# NextTouch.net
KiCad netlist of a schematic drawn in EAGLE
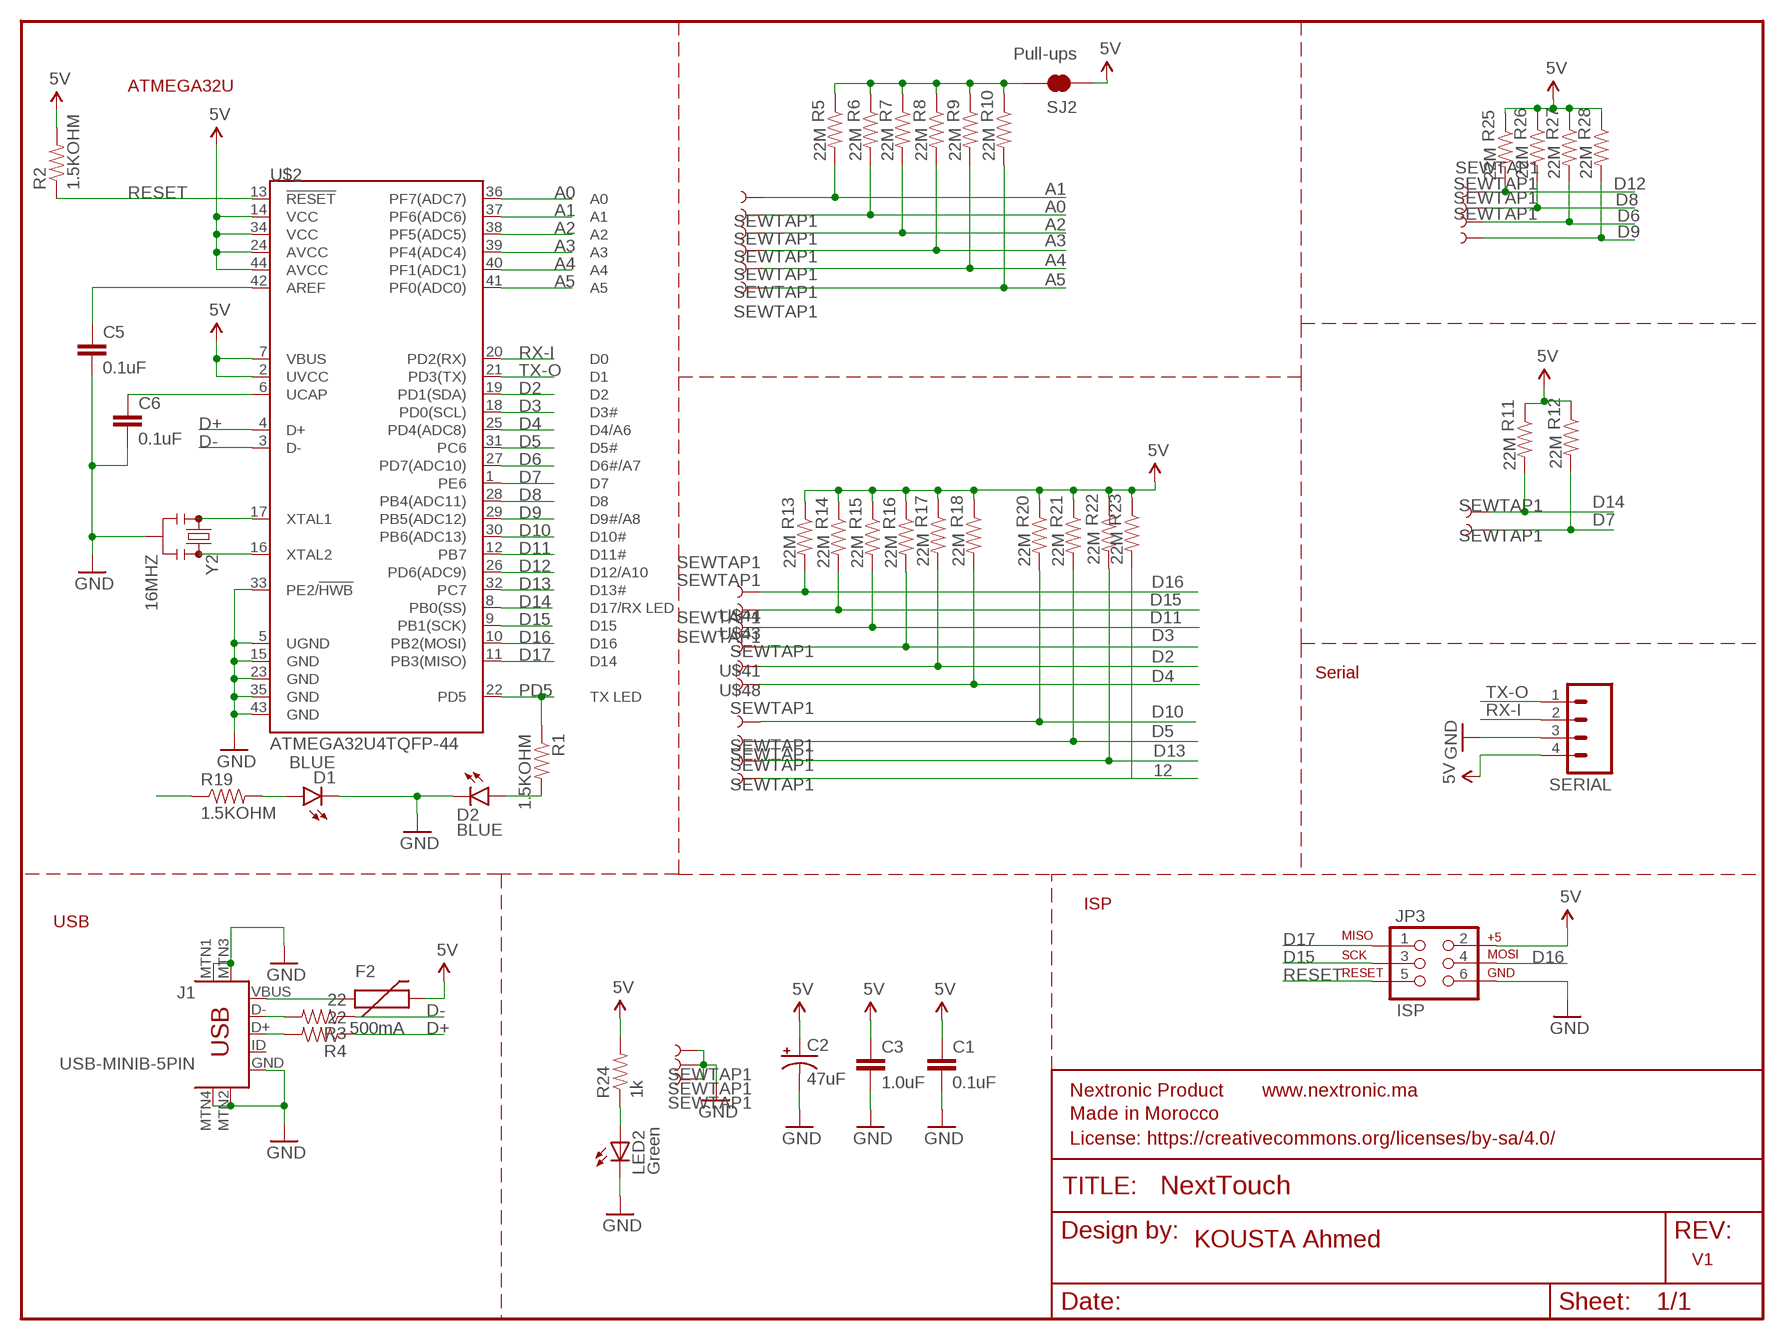
[diagram p0: schematic, sheet 1]

(export (version "E")
  (design (tool "Eeschema 10.0.6"))
  (components
    (comp (ref "C1")
      (value "0.1uF")
      (footprint "eagle-import:0603")
      (libsource (lib "eagle-import") (part "CAP0603"))
    )
    (comp (ref "C2")
      (value "47uF")
      (footprint "eagle-import:EIA3528")
      (libsource (lib "eagle-import") (part "CAP_POL3528"))
    )
    (comp (ref "C3")
      (value "1.0uF")
      (footprint "eagle-import:0603")
      (libsource (lib "eagle-import") (part "CAP0603"))
    )
    (comp (ref "C5")
      (value "0.1uF")
      (footprint "eagle-import:0603")
      (libsource (lib "eagle-import") (part "0.18UF-10V(+-10%)(0603)"))
    )
    (comp (ref "C6")
      (value "0.1uF")
      (footprint "eagle-import:0603")
      (libsource (lib "eagle-import") (part "0.18UF-10V(+-10%)(0603)"))
    )
    (comp (ref "D1")
      (value "BLUE")
      (footprint "eagle-import:LED-1206")
      (libsource (lib "eagle-import") (part "LED-BLUE1206"))
    )
    (comp (ref "D2")
      (value "BLUE")
      (footprint "eagle-import:LED-1206")
      (libsource (lib "eagle-import") (part "LED-BLUE1206"))
    )
    (comp (ref "F2")
      (value "500mA")
      (footprint "eagle-import:PTC-1206")
      (libsource (lib "eagle-import") (part "PTCSMD"))
    )
    (comp (ref "FRAME1")
      (value "FRAME-LETTER")
      (footprint "eagle-import:CREATIVE_COMMONS")
      (libsource (lib "eagle-import") (part "FRAME-LETTER"))
    )
    (comp (ref "GND")
      (value "SEWTAP1")
      (footprint "eagle-import:PETAL-LONG-1")
      (libsource (lib "eagle-import") (part "SEWTAP1"))
    )
    (comp (ref "J1")
      (value "USB-MINIB-5PIN")
      (footprint "eagle-import:USB-MINIB")
      (libsource (lib "eagle-import") (part "USB-MINIB-5PIN"))
    )
    (comp (ref "JP3")
      (value "ISP")
      (footprint "eagle-import:2X3-NS")
      (libsource (lib "eagle-import") (part "AVR_SPI_PRG_6NS"))
    )
    (comp (ref "LED2")
      (value "Green")
      (footprint "eagle-import:LED-1206-NO_SILK")
      (libsource (lib "eagle-import") (part "LED1206-NS"))
    )
    (comp (ref "R1")
      (value "1.5KOHM")
      (footprint "eagle-import:0603")
      (libsource (lib "eagle-import") (part "1.5KOHM-1/10W-1%(0603)"))
    )
    (comp (ref "R2")
      (value "1.5KOHM")
      (footprint "eagle-import:0603")
      (libsource (lib "eagle-import") (part "1.5KOHM-1/10W-1%(0603)"))
    )
    (comp (ref "R3")
      (value "22")
      (footprint "eagle-import:0603")
      (libsource (lib "eagle-import") (part "1.5KOHM-1/10W-1%(0603)"))
    )
    (comp (ref "R4")
      (value "22")
      (footprint "eagle-import:0603")
      (libsource (lib "eagle-import") (part "1.5KOHM-1/10W-1%(0603)"))
    )
    (comp (ref "R5")
      (value "22M")
      (footprint "eagle-import:0603")
      (libsource (lib "eagle-import") (part "1.5KOHM-1/10W-1%(0603)"))
    )
    (comp (ref "R6")
      (value "22M")
      (footprint "eagle-import:0603")
      (libsource (lib "eagle-import") (part "1.5KOHM-1/10W-1%(0603)"))
    )
    (comp (ref "R7")
      (value "22M")
      (footprint "eagle-import:0603")
      (libsource (lib "eagle-import") (part "1.5KOHM-1/10W-1%(0603)"))
    )
    (comp (ref "R8")
      (value "22M")
      (footprint "eagle-import:0603")
      (libsource (lib "eagle-import") (part "1.5KOHM-1/10W-1%(0603)"))
    )
    (comp (ref "R9")
      (value "22M")
      (footprint "eagle-import:0603")
      (libsource (lib "eagle-import") (part "1.5KOHM-1/10W-1%(0603)"))
    )
    (comp (ref "R10")
      (value "22M")
      (footprint "eagle-import:0603")
      (libsource (lib "eagle-import") (part "1.5KOHM-1/10W-1%(0603)"))
    )
    (comp (ref "R11")
      (value "22M")
      (footprint "eagle-import:0603")
      (libsource (lib "eagle-import") (part "1.5KOHM-1/10W-1%(0603)"))
    )
    (comp (ref "R12")
      (value "22M")
      (footprint "eagle-import:0603")
      (libsource (lib "eagle-import") (part "1.5KOHM-1/10W-1%(0603)"))
    )
    (comp (ref "R13")
      (value "22M")
      (footprint "eagle-import:0603")
      (libsource (lib "eagle-import") (part "1.5KOHM-1/10W-1%(0603)"))
    )
    (comp (ref "R14")
      (value "22M")
      (footprint "eagle-import:0603")
      (libsource (lib "eagle-import") (part "1.5KOHM-1/10W-1%(0603)"))
    )
    (comp (ref "R15")
      (value "22M")
      (footprint "eagle-import:0603")
      (libsource (lib "eagle-import") (part "1.5KOHM-1/10W-1%(0603)"))
    )
    (comp (ref "R16")
      (value "22M")
      (footprint "eagle-import:0603")
      (libsource (lib "eagle-import") (part "1.5KOHM-1/10W-1%(0603)"))
    )
    (comp (ref "R17")
      (value "22M")
      (footprint "eagle-import:0603")
      (libsource (lib "eagle-import") (part "1.5KOHM-1/10W-1%(0603)"))
    )
    (comp (ref "R18")
      (value "22M")
      (footprint "eagle-import:0603")
      (libsource (lib "eagle-import") (part "1.5KOHM-1/10W-1%(0603)"))
    )
    (comp (ref "R19")
      (value "1.5KOHM")
      (footprint "eagle-import:0603")
      (libsource (lib "eagle-import") (part "1.5KOHM-1/10W-1%(0603)"))
    )
    (comp (ref "R20")
      (value "22M")
      (footprint "eagle-import:0603")
      (libsource (lib "eagle-import") (part "1.5KOHM-1/10W-1%(0603)"))
    )
    (comp (ref "R21")
      (value "22M")
      (footprint "eagle-import:0603")
      (libsource (lib "eagle-import") (part "1.5KOHM-1/10W-1%(0603)"))
    )
    (comp (ref "R22")
      (value "22M")
      (footprint "eagle-import:0603")
      (libsource (lib "eagle-import") (part "1.5KOHM-1/10W-1%(0603)"))
    )
    (comp (ref "R23")
      (value "22M")
      (footprint "eagle-import:0603")
      (libsource (lib "eagle-import") (part "1.5KOHM-1/10W-1%(0603)"))
    )
    (comp (ref "R24")
      (value "1k")
      (footprint "eagle-import:0603-RES")
      (libsource (lib "eagle-import") (part "RESISTOR0603-RES"))
    )
    (comp (ref "R25")
      (value "22M")
      (footprint "eagle-import:0603")
      (libsource (lib "eagle-import") (part "1.5KOHM-1/10W-1%(0603)"))
    )
    (comp (ref "R26")
      (value "22M")
      (footprint "eagle-import:0603")
      (libsource (lib "eagle-import") (part "1.5KOHM-1/10W-1%(0603)"))
    )
    (comp (ref "R27")
      (value "22M")
      (footprint "eagle-import:0603")
      (libsource (lib "eagle-import") (part "1.5KOHM-1/10W-1%(0603)"))
    )
    (comp (ref "R28")
      (value "22M")
      (footprint "eagle-import:0603")
      (libsource (lib "eagle-import") (part "1.5KOHM-1/10W-1%(0603)"))
    )
    (comp (ref "SERIAL")
      (value "M04PTH")
      (footprint "eagle-import:1X04")
      (libsource (lib "eagle-import") (part "M04PTH"))
    )
    (comp (ref "SJ2")
      (value "Pull-ups")
      (footprint "eagle-import:SJ_2S-TRACE")
      (libsource (lib "eagle-import") (part "SOLDERJUMPER-OLDTRACE"))
    )
    (comp (ref "U$2")
      (value "ATMEGA32U4TQFP-44")
      (footprint "eagle-import:TQFP44")
      (libsource (lib "eagle-import") (part "ATMEGA32U4TQFP-44"))
    )
    (comp (ref "U$3")
      (value "SEWTAP1")
      (footprint "eagle-import:PETAL-LONG-1")
      (libsource (lib "eagle-import") (part "SEWTAP1"))
    )
    (comp (ref "U$4")
      (value "SEWTAP1")
      (footprint "eagle-import:PETAL-LONG-1")
      (libsource (lib "eagle-import") (part "SEWTAP1"))
    )
    (comp (ref "U$5")
      (value "SEWTAP1")
      (footprint "eagle-import:PETAL-LONG-1")
      (libsource (lib "eagle-import") (part "SEWTAP1"))
    )
    (comp (ref "U$6")
      (value "SEWTAP1")
      (footprint "eagle-import:PETAL-LONG-1")
      (libsource (lib "eagle-import") (part "SEWTAP1"))
    )
    (comp (ref "U$7")
      (value "SEWTAP1")
      (footprint "eagle-import:PETAL-LONG-1")
      (libsource (lib "eagle-import") (part "SEWTAP1"))
    )
    (comp (ref "U$30")
      (value "SEWTAP1")
      (footprint "eagle-import:PETAL-LONG-1")
      (libsource (lib "eagle-import") (part "SEWTAP1"))
    )
    (comp (ref "U$31")
      (value "SEWTAP1")
      (footprint "eagle-import:PETAL-LONG-1")
      (libsource (lib "eagle-import") (part "SEWTAP1"))
    )
    (comp (ref "U$32")
      (value "SEWTAP1")
      (footprint "eagle-import:PETAL-LONG-1")
      (libsource (lib "eagle-import") (part "SEWTAP1"))
    )
    (comp (ref "U$33")
      (value "SEWTAP1")
      (footprint "eagle-import:PETAL-LONG-1")
      (libsource (lib "eagle-import") (part "SEWTAP1"))
    )
    (comp (ref "U$34")
      (value "SEWTAP1")
      (footprint "eagle-import:PETAL-LONG-1")
      (libsource (lib "eagle-import") (part "SEWTAP1"))
    )
    (comp (ref "U$35")
      (value "SEWTAP1")
      (footprint "eagle-import:PETAL-LONG-1")
      (libsource (lib "eagle-import") (part "SEWTAP1"))
    )
    (comp (ref "U$36")
      (value "SEWTAP1")
      (footprint "eagle-import:PETAL-LONG-1")
      (libsource (lib "eagle-import") (part "SEWTAP1"))
    )
    (comp (ref "U$37")
      (value "SEWTAP1")
      (footprint "eagle-import:PETAL-LONG-1")
      (libsource (lib "eagle-import") (part "SEWTAP1"))
    )
    (comp (ref "U$38")
      (value "SEWTAP1")
      (footprint "eagle-import:PETAL-LONG-1")
      (libsource (lib "eagle-import") (part "SEWTAP1"))
    )
    (comp (ref "U$39")
      (value "SEWTAP1")
      (footprint "eagle-import:PETAL-LONG-1")
      (libsource (lib "eagle-import") (part "SEWTAP1"))
    )
    (comp (ref "U$40")
      (value "SEWTAP1")
      (footprint "eagle-import:PETAL-LONG-1")
      (libsource (lib "eagle-import") (part "SEWTAP1"))
    )
    (comp (ref "U$41")
      (value "SEWTAP1")
      (footprint "eagle-import:PETAL-LONG-1")
      (libsource (lib "eagle-import") (part "SEWTAP1"))
    )
    (comp (ref "U$42")
      (value "SEWTAP1")
      (footprint "eagle-import:PETAL-LONG-1")
      (libsource (lib "eagle-import") (part "SEWTAP1"))
    )
    (comp (ref "U$43")
      (value "SEWTAP1")
      (footprint "eagle-import:PETAL-LONG-1")
      (libsource (lib "eagle-import") (part "SEWTAP1"))
    )
    (comp (ref "U$44")
      (value "SEWTAP1")
      (footprint "eagle-import:PETAL-LONG-1")
      (libsource (lib "eagle-import") (part "SEWTAP1"))
    )
    (comp (ref "U$45")
      (value "SEWTAP1")
      (footprint "eagle-import:PETAL-LONG-1")
      (libsource (lib "eagle-import") (part "SEWTAP1"))
    )
    (comp (ref "U$46")
      (value "SEWTAP1")
      (footprint "eagle-import:PETAL-LONG-1")
      (libsource (lib "eagle-import") (part "SEWTAP1"))
    )
    (comp (ref "U$48")
      (value "SEWTAP1")
      (footprint "eagle-import:PETAL-LONG-1")
      (libsource (lib "eagle-import") (part "SEWTAP1"))
    )
    (comp (ref "U$51")
      (value "SEWTAP1")
      (footprint "eagle-import:PETAL-LONG-1")
      (libsource (lib "eagle-import") (part "SEWTAP1"))
    )
    (comp (ref "Y2")
      (value "16MHZ")
      (footprint "eagle-import:RESONATOR-SMD")
      (libsource (lib "eagle-import") (part "RESONATOR16MHZ"))
    )
  )
  (nets
    (net (code "1") (name "/12") (class "Default")
      (node (ref "R23") (pin "2") (pinfunction "2_2") (pintype "passive"))
      (node (ref "U$51") (pin "1") (pinfunction "1_1") (pintype "bidirectional"))
    )
    (net (code "2") (name "/A0") (class "Default")
      (node (ref "R6") (pin "2") (pinfunction "2_2") (pintype "passive"))
      (node (ref "U$2") (pin "36") (pinfunction "PF7(ADC7)_36") (pintype "bidirectional"))
      (node (ref "U$40") (pin "1") (pinfunction "1_1") (pintype "bidirectional"))
    )
    (net (code "3") (name "/A1") (class "Default")
      (node (ref "R5") (pin "2") (pinfunction "2_2") (pintype "passive"))
      (node (ref "U$2") (pin "37") (pinfunction "PF6(ADC6)_37") (pintype "bidirectional"))
      (node (ref "U$4") (pin "1") (pinfunction "1_1") (pintype "bidirectional"))
    )
    (net (code "4") (name "/A2") (class "Default")
      (node (ref "R7") (pin "2") (pinfunction "2_2") (pintype "passive"))
      (node (ref "U$2") (pin "38") (pinfunction "PF5(ADC5)_38") (pintype "bidirectional"))
      (node (ref "U$31") (pin "1") (pinfunction "1_1") (pintype "bidirectional"))
    )
    (net (code "5") (name "/A3") (class "Default")
      (node (ref "R8") (pin "2") (pinfunction "2_2") (pintype "passive"))
      (node (ref "U$2") (pin "39") (pinfunction "PF4(ADC4)_39") (pintype "bidirectional"))
      (node (ref "U$32") (pin "1") (pinfunction "1_1") (pintype "bidirectional"))
    )
    (net (code "6") (name "/A4") (class "Default")
      (node (ref "R9") (pin "2") (pinfunction "2_2") (pintype "passive"))
      (node (ref "U$2") (pin "40") (pinfunction "PF1(ADC1)_40") (pintype "bidirectional"))
      (node (ref "U$33") (pin "1") (pinfunction "1_1") (pintype "bidirectional"))
    )
    (net (code "7") (name "/A5") (class "Default")
      (node (ref "R10") (pin "2") (pinfunction "2_2") (pintype "passive"))
      (node (ref "U$2") (pin "41") (pinfunction "PF0(ADC0)_41") (pintype "bidirectional"))
      (node (ref "U$34") (pin "1") (pinfunction "1_1") (pintype "bidirectional"))
    )
    (net (code "8") (name "/D+") (class "Default")
      (node (ref "R4") (pin "1") (pinfunction "1_1") (pintype "passive"))
      (node (ref "U$2") (pin "4") (pinfunction "D+_4") (pintype "bidirectional"))
    )
    (net (code "9") (name "/D-") (class "Default")
      (node (ref "R3") (pin "1") (pinfunction "1_1") (pintype "passive"))
      (node (ref "U$2") (pin "3") (pinfunction "D-_3") (pintype "bidirectional"))
    )
    (net (code "10") (name "/D2") (class "Default")
      (node (ref "R17") (pin "2") (pinfunction "2_2") (pintype "passive"))
      (node (ref "U$2") (pin "19") (pinfunction "PD1(SDA)_19") (pintype "bidirectional"))
      (node (ref "U$48") (pin "1") (pinfunction "1_1") (pintype "bidirectional"))
    )
    (net (code "11") (name "/D3") (class "Default")
      (node (ref "R16") (pin "2") (pinfunction "2_2") (pintype "passive"))
      (node (ref "U$2") (pin "18") (pinfunction "PD0(SCL)_18") (pintype "bidirectional"))
      (node (ref "U$41") (pin "1") (pinfunction "1_1") (pintype "bidirectional"))
    )
    (net (code "12") (name "/D4") (class "Default")
      (node (ref "R18") (pin "2") (pinfunction "2_2") (pintype "passive"))
      (node (ref "U$2") (pin "25") (pinfunction "PD4(ADC8)_25") (pintype "bidirectional"))
      (node (ref "U$35") (pin "1") (pinfunction "1_1") (pintype "bidirectional"))
    )
    (net (code "13") (name "/D5") (class "Default")
      (node (ref "R21") (pin "2") (pinfunction "2_2") (pintype "passive"))
      (node (ref "U$2") (pin "31") (pinfunction "PC6_31") (pintype "bidirectional"))
      (node (ref "U$38") (pin "1") (pinfunction "1_1") (pintype "bidirectional"))
    )
    (net (code "14") (name "/D6") (class "Default")
      (node (ref "R27") (pin "2") (pinfunction "2_2") (pintype "passive"))
      (node (ref "U$2") (pin "27") (pinfunction "PD7(ADC10)_27") (pintype "bidirectional"))
      (node (ref "U$7") (pin "1") (pinfunction "1_1") (pintype "bidirectional"))
    )
    (net (code "15") (name "/D7") (class "Default")
      (node (ref "R12") (pin "2") (pinfunction "2_2") (pintype "passive"))
      (node (ref "U$2") (pin "1") (pinfunction "PE6_1") (pintype "bidirectional"))
      (node (ref "U$46") (pin "1") (pinfunction "1_1") (pintype "bidirectional"))
    )
    (net (code "16") (name "/D8") (class "Default")
      (node (ref "R26") (pin "2") (pinfunction "2_2") (pintype "passive"))
      (node (ref "U$2") (pin "28") (pinfunction "PB4(ADC11)_28") (pintype "bidirectional"))
      (node (ref "U$6") (pin "1") (pinfunction "1_1") (pintype "bidirectional"))
    )
    (net (code "17") (name "/D9") (class "Default")
      (node (ref "R28") (pin "2") (pinfunction "2_2") (pintype "passive"))
      (node (ref "U$2") (pin "29") (pinfunction "PB5(ADC12)_29") (pintype "bidirectional"))
      (node (ref "U$3") (pin "1") (pinfunction "1_1") (pintype "bidirectional"))
    )
    (net (code "18") (name "/D10") (class "Default")
      (node (ref "R20") (pin "2") (pinfunction "2_2") (pintype "passive"))
      (node (ref "U$2") (pin "30") (pinfunction "PB6(ADC13)_30") (pintype "bidirectional"))
      (node (ref "U$37") (pin "1") (pinfunction "1_1") (pintype "bidirectional"))
    )
    (net (code "19") (name "/D11") (class "Default")
      (node (ref "R15") (pin "2") (pinfunction "2_2") (pintype "passive"))
      (node (ref "U$2") (pin "12") (pinfunction "PB7_12") (pintype "bidirectional"))
      (node (ref "U$42") (pin "1") (pinfunction "1_1") (pintype "bidirectional"))
    )
    (net (code "20") (name "/D12") (class "Default")
      (node (ref "R25") (pin "2") (pinfunction "2_2") (pintype "passive"))
      (node (ref "U$2") (pin "26") (pinfunction "PD6(ADC9)_26") (pintype "bidirectional"))
      (node (ref "U$5") (pin "1") (pinfunction "1_1") (pintype "bidirectional"))
    )
    (net (code "21") (name "/D13") (class "Default")
      (node (ref "R22") (pin "2") (pinfunction "2_2") (pintype "passive"))
      (node (ref "U$2") (pin "32") (pinfunction "PC7_32") (pintype "bidirectional"))
      (node (ref "U$39") (pin "1") (pinfunction "1_1") (pintype "bidirectional"))
    )
    (net (code "22") (name "/D14") (class "Default")
      (node (ref "R11") (pin "2") (pinfunction "2_2") (pintype "passive"))
      (node (ref "U$2") (pin "8") (pinfunction "PB0(SS)_8") (pintype "bidirectional"))
      (node (ref "U$45") (pin "1") (pinfunction "1_1") (pintype "bidirectional"))
    )
    (net (code "23") (name "/D15") (class "Default")
      (node (ref "JP3") (pin "3") (pinfunction "3_3") (pintype "passive"))
      (node (ref "R14") (pin "2") (pinfunction "2_2") (pintype "passive"))
      (node (ref "U$2") (pin "9") (pinfunction "PB1(SCK)_9") (pintype "bidirectional"))
      (node (ref "U$43") (pin "1") (pinfunction "1_1") (pintype "bidirectional"))
    )
    (net (code "24") (name "/D16") (class "Default")
      (node (ref "JP3") (pin "4") (pinfunction "4_4") (pintype "passive"))
      (node (ref "R13") (pin "2") (pinfunction "2_2") (pintype "passive"))
      (node (ref "U$2") (pin "10") (pinfunction "PB2(MOSI)_10") (pintype "bidirectional"))
      (node (ref "U$44") (pin "1") (pinfunction "1_1") (pintype "bidirectional"))
    )
    (net (code "25") (name "/D17") (class "Default")
      (node (ref "JP3") (pin "1") (pinfunction "1_1") (pintype "passive"))
      (node (ref "R19") (pin "1") (pinfunction "1_1") (pintype "passive"))
      (node (ref "U$2") (pin "11") (pinfunction "PB3(MISO)_11") (pintype "bidirectional"))
    )
    (net (code "26") (name "/PD5") (class "Default")
      (node (ref "R1") (pin "1") (pinfunction "1_1") (pintype "passive"))
      (node (ref "U$2") (pin "22") (pinfunction "PD5_22") (pintype "bidirectional"))
    )
    (net (code "27") (name "/RESET") (class "Default")
      (node (ref "JP3") (pin "5") (pinfunction "5_5") (pintype "passive"))
      (node (ref "R2") (pin "1") (pinfunction "1_1") (pintype "passive"))
      (node (ref "U$2") (pin "13") (pinfunction "~{RESET}_13") (pintype "bidirectional"))
    )
    (net (code "28") (name "/RX-I") (class "Default")
      (node (ref "SERIAL") (pin "2") (pinfunction "2_2") (pintype "passive"))
      (node (ref "U$2") (pin "20") (pinfunction "PD2(RX)_20") (pintype "bidirectional"))
    )
    (net (code "29") (name "/TX-O") (class "Default")
      (node (ref "SERIAL") (pin "1") (pinfunction "1_1") (pintype "passive"))
      (node (ref "U$2") (pin "21") (pinfunction "PD3(TX)_21") (pintype "bidirectional"))
    )
    (net (code "30") (name "5V") (class "Default")
      (node (ref "C1") (pin "1") (pinfunction "1_1") (pintype "passive"))
      (node (ref "C2") (pin "A") (pinfunction "+_A") (pintype "passive"))
      (node (ref "C3") (pin "1") (pinfunction "1_1") (pintype "passive"))
      (node (ref "F2") (pin "2") (pinfunction "2_2") (pintype "bidirectional"))
      (node (ref "JP3") (pin "2") (pinfunction "2_2") (pintype "passive"))
      (node (ref "R11") (pin "1") (pinfunction "1_1") (pintype "passive"))
      (node (ref "R12") (pin "1") (pinfunction "1_1") (pintype "passive"))
      (node (ref "R13") (pin "1") (pinfunction "1_1") (pintype "passive"))
      (node (ref "R14") (pin "1") (pinfunction "1_1") (pintype "passive"))
      (node (ref "R15") (pin "1") (pinfunction "1_1") (pintype "passive"))
      (node (ref "R16") (pin "1") (pinfunction "1_1") (pintype "passive"))
      (node (ref "R17") (pin "1") (pinfunction "1_1") (pintype "passive"))
      (node (ref "R18") (pin "1") (pinfunction "1_1") (pintype "passive"))
      (node (ref "R2") (pin "2") (pinfunction "2_2") (pintype "passive"))
      (node (ref "R20") (pin "1") (pinfunction "1_1") (pintype "passive"))
      (node (ref "R21") (pin "1") (pinfunction "1_1") (pintype "passive"))
      (node (ref "R22") (pin "1") (pinfunction "1_1") (pintype "passive"))
      (node (ref "R23") (pin "1") (pinfunction "1_1") (pintype "passive"))
      (node (ref "R24") (pin "2") (pinfunction "2_2") (pintype "passive"))
      (node (ref "R25") (pin "1") (pinfunction "1_1") (pintype "passive"))
      (node (ref "R26") (pin "1") (pinfunction "1_1") (pintype "passive"))
      (node (ref "R27") (pin "1") (pinfunction "1_1") (pintype "passive"))
      (node (ref "R28") (pin "1") (pinfunction "1_1") (pintype "passive"))
      (node (ref "SERIAL") (pin "4") (pinfunction "4_4") (pintype "passive"))
      (node (ref "SJ2") (pin "1") (pinfunction "1_1") (pintype "passive"))
      (node (ref "U$2") (pin "14") (pinfunction "VCC_14") (pintype "bidirectional"))
      (node (ref "U$2") (pin "2") (pinfunction "UVCC_2") (pintype "bidirectional"))
      (node (ref "U$2") (pin "24") (pinfunction "AVCC_24") (pintype "bidirectional"))
      (node (ref "U$2") (pin "34") (pinfunction "VCC_34") (pintype "bidirectional"))
      (node (ref "U$2") (pin "44") (pinfunction "AVCC_44") (pintype "bidirectional"))
      (node (ref "U$2") (pin "7") (pinfunction "VBUS_7") (pintype "bidirectional"))
    )
    (net (code "31") (name "GND") (class "Default")
      (node (ref "C1") (pin "2") (pinfunction "2_2") (pintype "passive"))
      (node (ref "C2") (pin "C") (pinfunction "-_C") (pintype "passive"))
      (node (ref "C3") (pin "2") (pinfunction "2_2") (pintype "passive"))
      (node (ref "C5") (pin "2") (pinfunction "2_2") (pintype "passive"))
      (node (ref "C6") (pin "2") (pinfunction "2_2") (pintype "passive"))
      (node (ref "D1") (pin "C") (pinfunction "C_C") (pintype "passive"))
      (node (ref "D2") (pin "C") (pinfunction "C_C") (pintype "passive"))
      (node (ref "GND") (pin "1") (pinfunction "1_1") (pintype "bidirectional"))
      (node (ref "J1") (pin "GND") (pinfunction "GND_GND") (pintype "bidirectional"))
      (node (ref "J1") (pin "MTN1") (pinfunction "MTN2_MTN1") (pintype "bidirectional"))
      (node (ref "J1") (pin "MTN2") (pinfunction "MTN3_MTN2") (pintype "bidirectional"))
      (node (ref "J1") (pin "MTN3") (pinfunction "MTN1_MTN3") (pintype "bidirectional"))
      (node (ref "J1") (pin "MTN4") (pinfunction "MTN4_MTN4") (pintype "bidirectional"))
      (node (ref "JP3") (pin "6") (pinfunction "6_6") (pintype "passive"))
      (node (ref "LED2") (pin "C") (pinfunction "C_C") (pintype "passive"))
      (node (ref "SERIAL") (pin "3") (pinfunction "3_3") (pintype "passive"))
      (node (ref "U$2") (pin "15") (pinfunction "GND_15") (pintype "bidirectional"))
      (node (ref "U$2") (pin "23") (pinfunction "GND_23") (pintype "bidirectional"))
      (node (ref "U$2") (pin "33") (pinfunction "PE2/~{HWB}_33") (pintype "bidirectional"))
      (node (ref "U$2") (pin "35") (pinfunction "GND_35") (pintype "bidirectional"))
      (node (ref "U$2") (pin "43") (pinfunction "GND_43") (pintype "bidirectional"))
      (node (ref "U$2") (pin "5") (pinfunction "UGND_5") (pintype "bidirectional"))
      (node (ref "U$30") (pin "1") (pinfunction "1_1") (pintype "bidirectional"))
      (node (ref "U$36") (pin "1") (pinfunction "1_1") (pintype "bidirectional"))
      (node (ref "Y2") (pin "2") (pinfunction "2_2") (pintype "passive"))
    )
    (net (code "32") (name "Net-(D1-PadA)") (class "Default")
      (node (ref "D1") (pin "A") (pinfunction "A_A") (pintype "passive"))
      (node (ref "R19") (pin "2") (pinfunction "2_2") (pintype "passive"))
    )
    (net (code "33") (name "Net-(D2-PadA)") (class "Default")
      (node (ref "D2") (pin "A") (pinfunction "A_A") (pintype "passive"))
      (node (ref "R1") (pin "2") (pinfunction "2_2") (pintype "passive"))
    )
    (net (code "34") (name "Net-(F2-Pad1)") (class "Default")
      (node (ref "F2") (pin "1") (pinfunction "1_1") (pintype "bidirectional"))
      (node (ref "J1") (pin "VBUS") (pinfunction "VBUS_VBUS") (pintype "bidirectional"))
    )
    (net (code "35") (name "Net-(J1-PadD+)") (class "Default")
      (node (ref "J1") (pin "D+") (pinfunction "D+_D+") (pintype "bidirectional"))
      (node (ref "R4") (pin "2") (pinfunction "2_2") (pintype "passive"))
    )
    (net (code "36") (name "Net-(J1-PadD-)") (class "Default")
      (node (ref "J1") (pin "D-") (pinfunction "D-_D-") (pintype "bidirectional"))
      (node (ref "R3") (pin "2") (pinfunction "2_2") (pintype "passive"))
    )
    (net (code "37") (name "Net-(LED2-PadA)") (class "Default")
      (node (ref "LED2") (pin "A") (pinfunction "A_A") (pintype "passive"))
      (node (ref "R24") (pin "1") (pinfunction "1_1") (pintype "passive"))
    )
    (net (code "38") (name "Net-(R10-Pad1)") (class "Default")
      (node (ref "R10") (pin "1") (pinfunction "1_1") (pintype "passive"))
      (node (ref "R5") (pin "1") (pinfunction "1_1") (pintype "passive"))
      (node (ref "R6") (pin "1") (pinfunction "1_1") (pintype "passive"))
      (node (ref "R7") (pin "1") (pinfunction "1_1") (pintype "passive"))
      (node (ref "R8") (pin "1") (pinfunction "1_1") (pintype "passive"))
      (node (ref "R9") (pin "1") (pinfunction "1_1") (pintype "passive"))
      (node (ref "SJ2") (pin "2") (pinfunction "2_2") (pintype "passive"))
    )
    (net (code "39") (name "Net-(U$2-AREF)") (class "Default")
      (node (ref "C5") (pin "1") (pinfunction "1_1") (pintype "passive"))
      (node (ref "U$2") (pin "42") (pinfunction "AREF_42") (pintype "bidirectional"))
    )
    (net (code "40") (name "Net-(U$2-UCAP)") (class "Default")
      (node (ref "C6") (pin "1") (pinfunction "1_1") (pintype "passive"))
      (node (ref "U$2") (pin "6") (pinfunction "UCAP_6") (pintype "bidirectional"))
    )
    (net (code "41") (name "Net-(U$2-XTAL1)") (class "Default")
      (node (ref "U$2") (pin "17") (pinfunction "XTAL1_17") (pintype "bidirectional"))
      (node (ref "Y2") (pin "1") (pinfunction "1_1") (pintype "passive"))
    )
    (net (code "42") (name "Net-(U$2-XTAL2)") (class "Default")
      (node (ref "U$2") (pin "16") (pinfunction "XTAL2_16") (pintype "bidirectional"))
      (node (ref "Y2") (pin "3") (pinfunction "3_3") (pintype "passive"))
    )
    (net (code "43") (name "unconnected-(J1-PadID)") (class "Default")
      (node (ref "J1") (pin "ID") (pinfunction "ID_ID") (pintype "bidirectional"))
    )
  )
)
